# BatteryChargerConn.net
KiCad netlist of a schematic drawn in Altium Designer
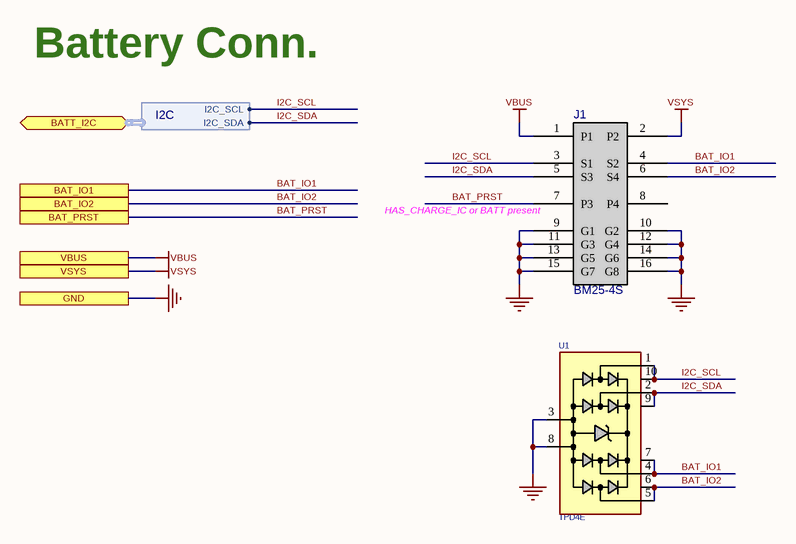
[diagram p0: BatteryChargerConn.SchDoc]

(export (version "E")
  (design (tool "Eeschema 10.0.6"))
  (components
    (comp (ref "J1")
      (value "BM25-4S")
      (footprint "BM25_4S")
      (description "BM25 Series B2B Connectors")
      (fields (field (name "MANF") "HIROSE") (field (name "MANF_P#") "BM25-4S_2-V(53)"))
      (libsource (lib "conn_b2b") (part "BM25-4S"))
    )
    (comp (ref "U1")
      (value "TPD4E")
      (footprint "SON50_10_2510E")
      (description "TVS, ESD PROTECT, 4CH,")
      (fields (field (name "MANF_P#") "TPD4E05U06DQA") (field (name "MANF") "Texas Instruments"))
      (libsource (lib "protect_tvs_esd_fuse") (part "TVS_X4_TPD4E05U06"))
    )
  )
  (nets
    (net (code "2") (name "/BAT_IO1") (class "Default")
      (node (ref "J1") (pin "4") (pinfunction "S2_4") (pintype "passive"))
      (node (ref "U1") (pin "4") (pinfunction "4_4") (pintype "passive"))
      (node (ref "U1") (pin "7") (pinfunction "7_7") (pintype "passive"))
    )
    (net (code "3") (name "/BAT_IO2") (class "Default")
      (node (ref "J1") (pin "6") (pinfunction "S4_6") (pintype "passive"))
      (node (ref "U1") (pin "5") (pinfunction "5_5") (pintype "passive"))
      (node (ref "U1") (pin "6") (pinfunction "6_6") (pintype "passive"))
    )
    (net (code "4") (name "/BAT_PRST") (class "Default")
      (node (ref "J1") (pin "7") (pinfunction "P3_7") (pintype "passive"))
    )
    (net (code "5") (name "/I2C_SCL") (class "Default")
      (node (ref "J1") (pin "3") (pinfunction "S1_3") (pintype "passive"))
      (node (ref "U1") (pin "1") (pinfunction "1_1") (pintype "passive"))
      (node (ref "U1") (pin "10") (pinfunction "10_10") (pintype "passive"))
    )
    (net (code "6") (name "/I2C_SDA") (class "Default")
      (node (ref "J1") (pin "5") (pinfunction "S3_5") (pintype "passive"))
      (node (ref "U1") (pin "2") (pinfunction "2_2") (pintype "passive"))
      (node (ref "U1") (pin "9") (pinfunction "9_9") (pintype "passive"))
    )
    (net (code "8") (name "GND") (class "Default")
      (node (ref "J1") (pin "10") (pinfunction "G2_10") (pintype "passive"))
      (node (ref "J1") (pin "11") (pinfunction "G3_11") (pintype "passive"))
      (node (ref "J1") (pin "12") (pinfunction "G4_12") (pintype "passive"))
      (node (ref "J1") (pin "13") (pinfunction "G5_13") (pintype "passive"))
      (node (ref "J1") (pin "14") (pinfunction "G6_14") (pintype "passive"))
      (node (ref "J1") (pin "15") (pinfunction "G7_15") (pintype "passive"))
      (node (ref "J1") (pin "16") (pinfunction "G8_16") (pintype "passive"))
      (node (ref "J1") (pin "9") (pinfunction "G1_9") (pintype "passive"))
      (node (ref "U1") (pin "3") (pinfunction "3_3") (pintype "passive"))
      (node (ref "U1") (pin "8") (pinfunction "8_8") (pintype "passive"))
    )
    (net (code "9") (name "VBUS") (class "Default")
      (node (ref "J1") (pin "1") (pinfunction "P1_1") (pintype "power_in"))
    )
    (net (code "10") (name "VSYS") (class "Default")
      (node (ref "J1") (pin "2") (pinfunction "P2_2") (pintype "power_in"))
    )
    (net (code "11") (name "unconnected-(J1-P4-Pad8)") (class "Default")
      (node (ref "J1") (pin "8") (pinfunction "P4_8") (pintype "passive"))
    )
  )
)
